# PARKPCB.net
KiCad netlist of a schematic drawn in EAGLE
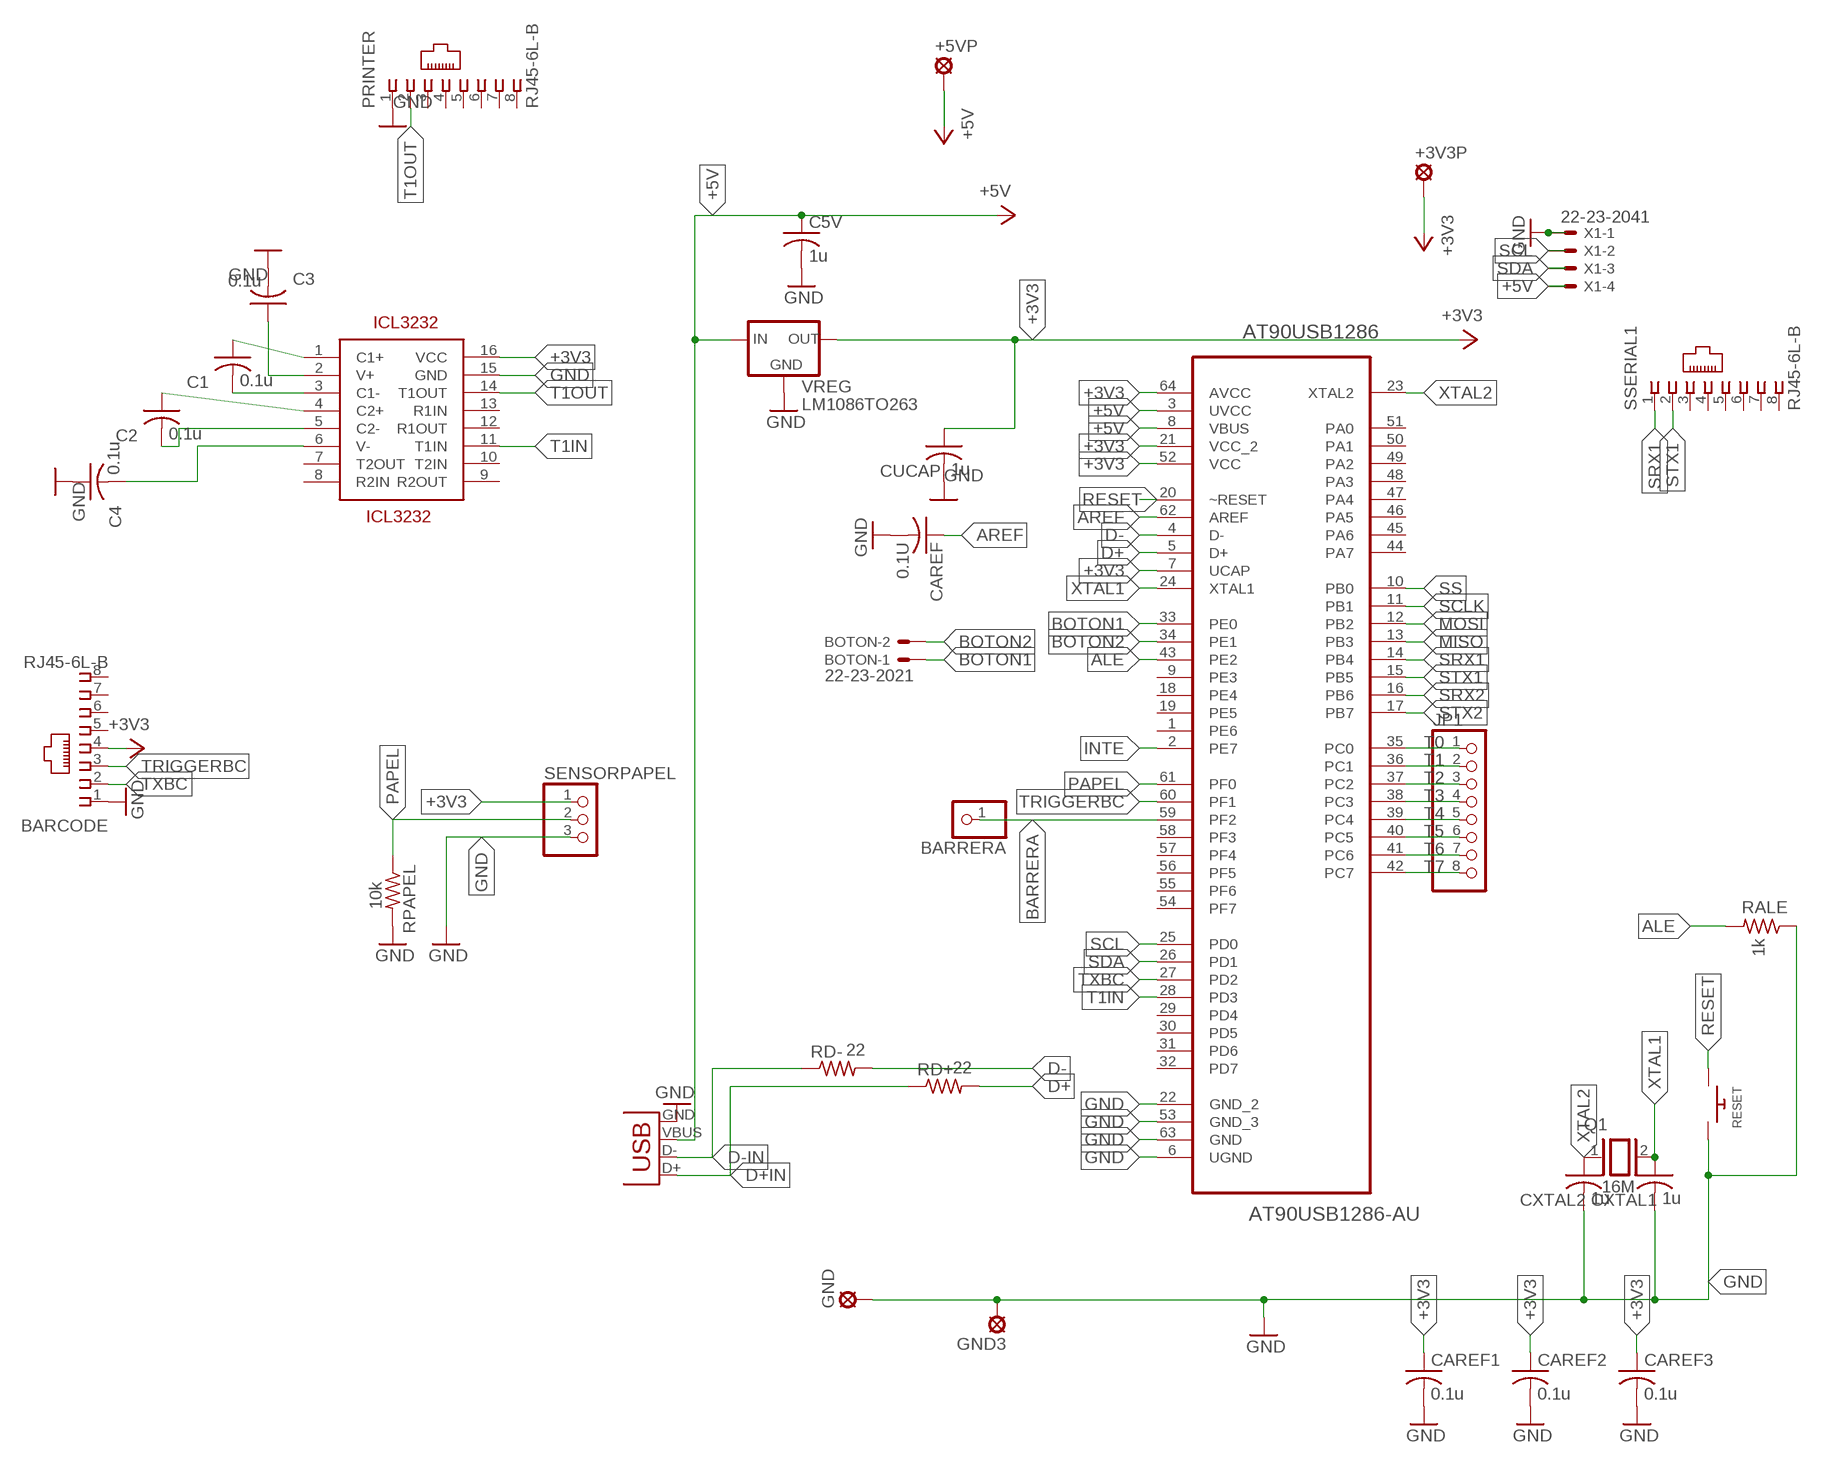
[diagram p0: schematic, sheet 1, part 1 of 2]
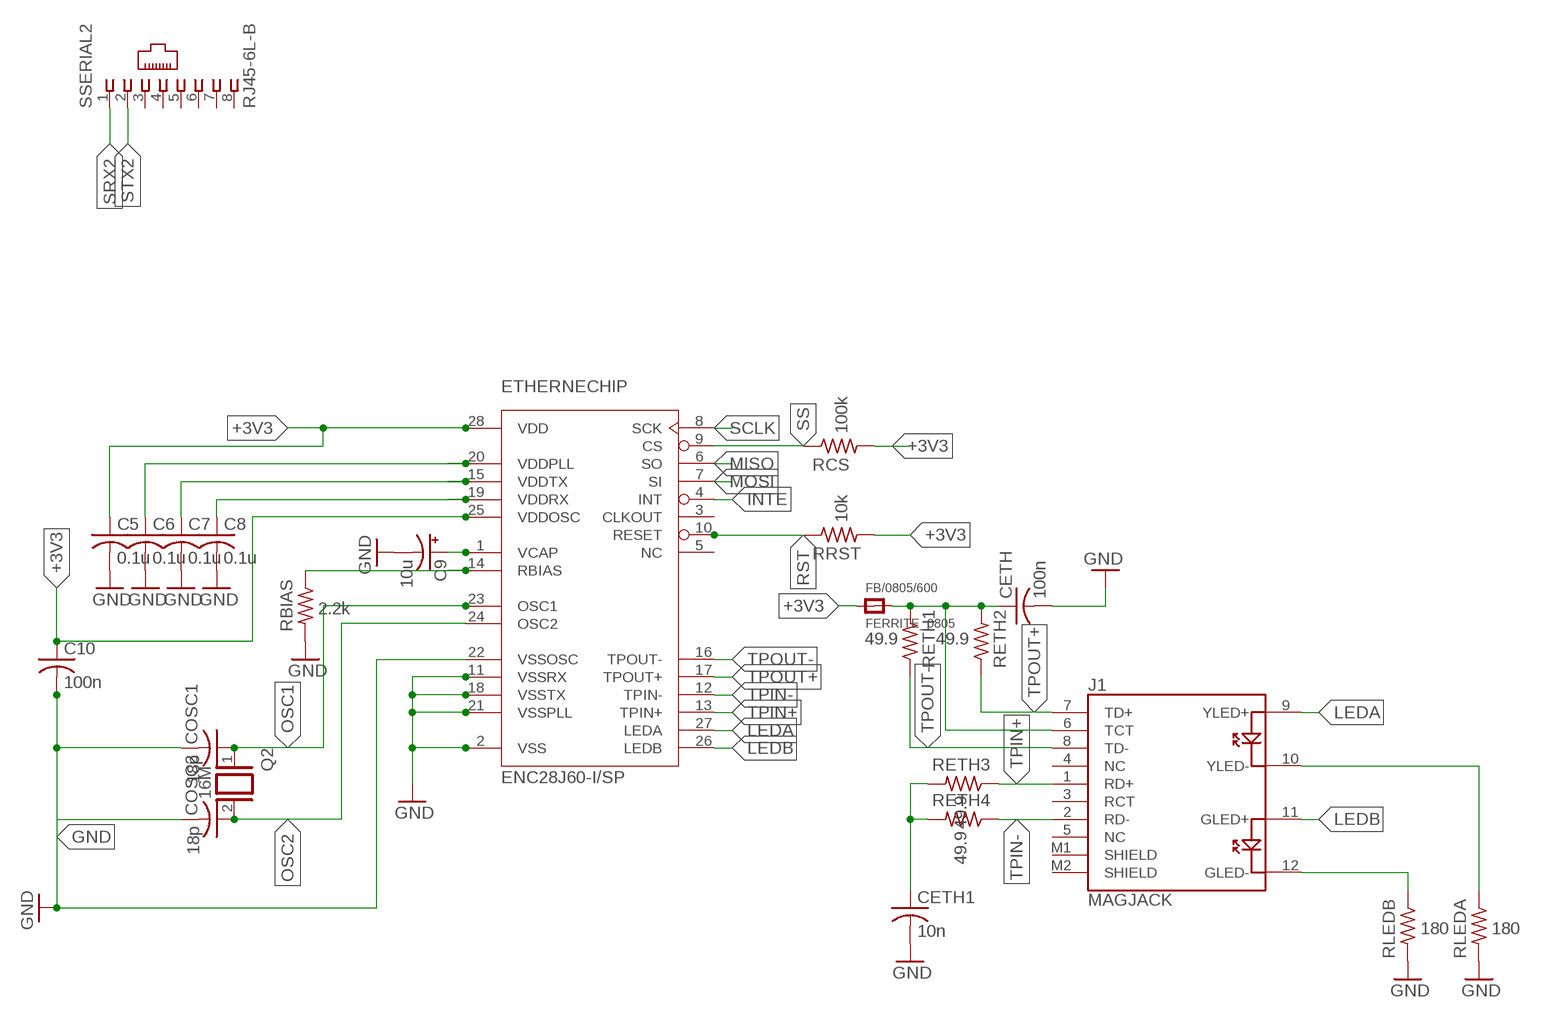
[diagram p1: schematic, sheet 1, part 2 of 2]

(export (version "E")
  (design (tool "Eeschema 10.0.6"))
  (components
    (comp (ref "+3V3P")
      (value "LSP10")
      (footprint "eagle-import:LSP10")
      (libsource (lib "eagle-import") (part "LSP10"))
    )
    (comp (ref "+5VP")
      (value "LSP10")
      (footprint "eagle-import:LSP10")
      (libsource (lib "eagle-import") (part "LSP10"))
    )
    (comp (ref "AT90USB1286")
      (value "AT90USB1286-AU")
      (footprint "eagle-import:QFP80P1600X1600X120-64N")
      (libsource (lib "eagle-import") (part "AT90USB1286-AU"))
    )
    (comp (ref "BARCODE")
      (value "RJ45-6L-B")
      (footprint "eagle-import:RJ45-NO-SHIELD")
      (libsource (lib "eagle-import") (part "RJ45-6L-B"))
    )
    (comp (ref "BARRERA")
      (value "PINHD-1X1")
      (footprint "eagle-import:1X01")
      (libsource (lib "eagle-import") (part "PINHD-1X1"))
    )
    (comp (ref "BOTON")
      (value "22-23-2021")
      (footprint "eagle-import:22-23-2021")
      (fields (field (name "MF") "MOLEX"))
      (libsource (lib "eagle-import") (part "22-23-2021"))
    )
    (comp (ref "C1")
      (value "0.1u")
      (footprint "eagle-import:C050-030X075")
      (libsource (lib "eagle-import") (part "C-US050-030X075"))
    )
    (comp (ref "C2")
      (value "0.1u")
      (footprint "eagle-import:C050-030X075")
      (libsource (lib "eagle-import") (part "C-US050-030X075"))
    )
    (comp (ref "C3")
      (value "0.1u")
      (footprint "eagle-import:C050-030X075")
      (libsource (lib "eagle-import") (part "C-US050-030X075"))
    )
    (comp (ref "C4")
      (value "0.1u")
      (footprint "eagle-import:C050-030X075")
      (libsource (lib "eagle-import") (part "C-US050-030X075"))
    )
    (comp (ref "C5")
      (value "0.1u")
      (footprint "eagle-import:C050-030X075")
      (libsource (lib "eagle-import") (part "C-US050-030X075"))
    )
    (comp (ref "C5V")
      (value "1u")
      (footprint "eagle-import:C050-030X075")
      (libsource (lib "eagle-import") (part "C-US050-030X075"))
    )
    (comp (ref "C6")
      (value "0.1u")
      (footprint "eagle-import:C050-030X075")
      (libsource (lib "eagle-import") (part "C-US050-030X075"))
    )
    (comp (ref "C7")
      (value "0.1u")
      (footprint "eagle-import:C050-030X075")
      (libsource (lib "eagle-import") (part "C-US050-030X075"))
    )
    (comp (ref "C8")
      (value "0.1u")
      (footprint "eagle-import:C050-030X075")
      (libsource (lib "eagle-import") (part "C-US050-030X075"))
    )
    (comp (ref "C9")
      (value "10u")
      (footprint "eagle-import:B45181B")
      (libsource (lib "eagle-import") (part "CPOL-USB45181B"))
    )
    (comp (ref "C10")
      (value "100n")
      (footprint "eagle-import:C050-030X075")
      (libsource (lib "eagle-import") (part "C-US050-030X075"))
    )
    (comp (ref "CAREF")
      (value "0.1U")
      (footprint "eagle-import:C050-030X075")
      (libsource (lib "eagle-import") (part "C-US050-030X075"))
    )
    (comp (ref "CAREF1")
      (value "0.1u")
      (footprint "eagle-import:C050-030X075")
      (libsource (lib "eagle-import") (part "C-US050-030X075"))
    )
    (comp (ref "CAREF2")
      (value "0.1u")
      (footprint "eagle-import:C050-030X075")
      (libsource (lib "eagle-import") (part "C-US050-030X075"))
    )
    (comp (ref "CAREF3")
      (value "0.1u")
      (footprint "eagle-import:C050-030X075")
      (libsource (lib "eagle-import") (part "C-US050-030X075"))
    )
    (comp (ref "CETH")
      (value "100n")
      (footprint "eagle-import:C050-030X075")
      (libsource (lib "eagle-import") (part "C-US050-030X075"))
    )
    (comp (ref "CETH1")
      (value "10n")
      (footprint "eagle-import:C050-030X075")
      (libsource (lib "eagle-import") (part "C-US050-030X075"))
    )
    (comp (ref "COSC1")
      (value "18p")
      (footprint "eagle-import:C050-030X075")
      (libsource (lib "eagle-import") (part "C-US050-030X075"))
    )
    (comp (ref "COSC2")
      (value "18p")
      (footprint "eagle-import:C050-030X075")
      (libsource (lib "eagle-import") (part "C-US050-030X075"))
    )
    (comp (ref "CUCAP")
      (value "1u")
      (footprint "eagle-import:C050-030X075")
      (libsource (lib "eagle-import") (part "C-US050-030X075"))
    )
    (comp (ref "CXTAL1")
      (value "1u")
      (footprint "eagle-import:C050-030X075")
      (libsource (lib "eagle-import") (part "C-US050-030X075"))
    )
    (comp (ref "CXTAL2")
      (value "1u")
      (footprint "eagle-import:C050-030X075")
      (libsource (lib "eagle-import") (part "C-US050-030X075"))
    )
    (comp (ref "ETHERNECHIP")
      (value "ENC28J60-I/SP")
      (footprint "eagle-import:DIP28")
      (libsource (lib "eagle-import") (part "ENC28J60-I/SP"))
    )
    (comp (ref "FB/0805/600")
      (value "FERRITE_0805")
      (footprint "eagle-import:_0805")
      (libsource (lib "eagle-import") (part "FERRITE_0805"))
    )
    (comp (ref "GND")
      (value "LSP10")
      (footprint "eagle-import:LSP10")
      (libsource (lib "eagle-import") (part "LSP10"))
    )
    (comp (ref "GND3")
      (value "LSP10")
      (footprint "eagle-import:LSP10")
      (libsource (lib "eagle-import") (part "LSP10"))
    )
    (comp (ref "ICL3232")
      (value "ICL3232")
      (footprint "eagle-import:DIL16")
      (fields (field (name "MF") "Intersil"))
      (libsource (lib "eagle-import") (part "ICL3232"))
    )
    (comp (ref "J1")
      (value "MAGJACK")
      (footprint "eagle-import:MAGJACK")
      (libsource (lib "eagle-import") (part "MAGJACK"))
    )
    (comp (ref "JP1")
      (value "PINHD-1X8BIG")
      (footprint "eagle-import:1X08-BIG")
      (libsource (lib "eagle-import") (part "PINHD-1X8BIG"))
    )
    (comp (ref "PRINTER")
      (value "RJ45-6L-B")
      (footprint "eagle-import:RJ45-NO-SHIELD")
      (libsource (lib "eagle-import") (part "RJ45-6L-B"))
    )
    (comp (ref "Q1")
      (value "16M")
      (footprint "eagle-import:QS")
      (libsource (lib "eagle-import") (part "XTAL/S"))
    )
    (comp (ref "Q2")
      (value "16M")
      (footprint "eagle-import:QS")
      (libsource (lib "eagle-import") (part "XTAL/S"))
    )
    (comp (ref "RALE")
      (value "1k")
      (footprint "eagle-import:0309_12")
      (libsource (lib "eagle-import") (part "R-US_0309/12"))
    )
    (comp (ref "RBIAS")
      (value "2.2k")
      (footprint "eagle-import:0309_12")
      (libsource (lib "eagle-import") (part "R-US_0309/12"))
    )
    (comp (ref "RCS")
      (value "100k")
      (footprint "eagle-import:0309_12")
      (libsource (lib "eagle-import") (part "R-US_0309/12"))
    )
    (comp (ref "RD+")
      (value "22")
      (footprint "eagle-import:0309_12")
      (libsource (lib "eagle-import") (part "R-US_0309/12"))
    )
    (comp (ref "RD-")
      (value "22")
      (footprint "eagle-import:0309_12")
      (libsource (lib "eagle-import") (part "R-US_0309/12"))
    )
    (comp (ref "RESET")
      (value "SWITCH_PUSHBUTTONC&K_KSS")
      (footprint "eagle-import:BTN_CK_KSS")
      (libsource (lib "eagle-import") (part "SWITCH_PUSHBUTTONC&K_KSS"))
    )
    (comp (ref "RETH1")
      (value "49.9")
      (footprint "eagle-import:0309_12")
      (libsource (lib "eagle-import") (part "R-US_0309/12"))
    )
    (comp (ref "RETH2")
      (value "49.9")
      (footprint "eagle-import:0309_12")
      (libsource (lib "eagle-import") (part "R-US_0309/12"))
    )
    (comp (ref "RETH3")
      (value "49.9")
      (footprint "eagle-import:0309_12")
      (libsource (lib "eagle-import") (part "R-US_0309/12"))
    )
    (comp (ref "RETH4")
      (value "49.9")
      (footprint "eagle-import:0309_12")
      (libsource (lib "eagle-import") (part "R-US_0309/12"))
    )
    (comp (ref "RLEDA")
      (value "180")
      (footprint "eagle-import:0309_12")
      (libsource (lib "eagle-import") (part "R-US_0309/12"))
    )
    (comp (ref "RLEDB")
      (value "180")
      (footprint "eagle-import:0309_12")
      (libsource (lib "eagle-import") (part "R-US_0309/12"))
    )
    (comp (ref "RPAPEL")
      (value "10k")
      (footprint "eagle-import:0309_12")
      (libsource (lib "eagle-import") (part "R-US_0309/12"))
    )
    (comp (ref "RRST")
      (value "10k")
      (footprint "eagle-import:0309_12")
      (libsource (lib "eagle-import") (part "R-US_0309/12"))
    )
    (comp (ref "SENSORPAPEL")
      (value "PINHD-1X3")
      (footprint "eagle-import:1X03")
      (libsource (lib "eagle-import") (part "PINHD-1X3"))
    )
    (comp (ref "SSERIAL1")
      (value "RJ45-6L-B")
      (footprint "eagle-import:RJ45-NO-SHIELD")
      (libsource (lib "eagle-import") (part "RJ45-6L-B"))
    )
    (comp (ref "SSERIAL2")
      (value "RJ45-6L-B")
      (footprint "eagle-import:RJ45-NO-SHIELD")
      (libsource (lib "eagle-import") (part "RJ45-6L-B"))
    )
    (comp (ref "USB")
      (value "USB-MB-S")
      (footprint "eagle-import:USB-MB-S")
      (libsource (lib "eagle-import") (part "USB-MB-S"))
    )
    (comp (ref "VREG")
      (value "LM1086TO263")
      (footprint "eagle-import:TO263")
      (libsource (lib "eagle-import") (part "LM1086TO263"))
    )
    (comp (ref "X1")
      (value "22-23-2041")
      (footprint "eagle-import:22-23-2041")
      (fields (field (name "MF") "MOLEX"))
      (libsource (lib "eagle-import") (part "22-23-2041"))
    )
  )
  (nets
    (net (code "1") (name "+3V3") (class "Default")
      (node (ref "+3V3P") (pin "MP") (pinfunction "MP_MP") (pintype "passive"))
      (node (ref "AT90USB1286") (pin "21") (pinfunction "VCC_2_21") (pintype "power_in"))
      (node (ref "AT90USB1286") (pin "52") (pinfunction "VCC_52") (pintype "power_in"))
      (node (ref "AT90USB1286") (pin "64") (pinfunction "AVCC_64") (pintype "power_in"))
      (node (ref "AT90USB1286") (pin "7") (pinfunction "UCAP_7") (pintype "passive"))
      (node (ref "BARCODE") (pin "4") (pinfunction "4_4") (pintype "passive"))
      (node (ref "C10") (pin "1") (pinfunction "1_1") (pintype "passive"))
      (node (ref "C5") (pin "1") (pinfunction "1_1") (pintype "passive"))
      (node (ref "CAREF1") (pin "1") (pinfunction "1_1") (pintype "passive"))
      (node (ref "CAREF2") (pin "1") (pinfunction "1_1") (pintype "passive"))
      (node (ref "CAREF3") (pin "1") (pinfunction "1_1") (pintype "passive"))
      (node (ref "CUCAP") (pin "1") (pinfunction "1_1") (pintype "passive"))
      (node (ref "ETHERNECHIP") (pin "25") (pinfunction "VDDOSC_25") (pintype "power_in"))
      (node (ref "ETHERNECHIP") (pin "28") (pinfunction "VDD_28") (pintype "power_in"))
      (node (ref "FB/0805/600") (pin "1") (pinfunction "P$1_1") (pintype "passive"))
      (node (ref "ICL3232") (pin "16") (pinfunction "VCC_16") (pintype "bidirectional"))
      (node (ref "RCS") (pin "2") (pinfunction "2_2") (pintype "passive"))
      (node (ref "RRST") (pin "2") (pinfunction "2_2") (pintype "passive"))
      (node (ref "SENSORPAPEL") (pin "1") (pinfunction "1_1") (pintype "passive"))
      (node (ref "VREG") (pin "2") (pinfunction "OUT_2") (pintype "passive"))
    )
    (net (code "2") (name "+5V") (class "Default")
      (node (ref "+5VP") (pin "MP") (pinfunction "MP_MP") (pintype "passive"))
      (node (ref "AT90USB1286") (pin "3") (pinfunction "UVCC_3") (pintype "power_in"))
      (node (ref "AT90USB1286") (pin "8") (pinfunction "VBUS_8") (pintype "power_in"))
      (node (ref "C5V") (pin "1") (pinfunction "1_1") (pintype "passive"))
      (node (ref "USB") (pin "VBUS") (pinfunction "VBUS_VBUS") (pintype "bidirectional"))
      (node (ref "VREG") (pin "3") (pinfunction "IN_3") (pintype "input"))
      (node (ref "X1") (pin "4") (pinfunction "S_4") (pintype "passive"))
    )
    (net (code "3") (name "/T0") (class "Default")
      (node (ref "AT90USB1286") (pin "35") (pinfunction "PC0_35") (pintype "bidirectional"))
      (node (ref "JP1") (pin "1") (pinfunction "1_1") (pintype "passive"))
    )
    (net (code "4") (name "/T1") (class "Default")
      (node (ref "AT90USB1286") (pin "36") (pinfunction "PC1_36") (pintype "bidirectional"))
      (node (ref "JP1") (pin "2") (pinfunction "2_2") (pintype "passive"))
    )
    (net (code "5") (name "/T2") (class "Default")
      (node (ref "AT90USB1286") (pin "37") (pinfunction "PC2_37") (pintype "bidirectional"))
      (node (ref "JP1") (pin "3") (pinfunction "3_3") (pintype "passive"))
    )
    (net (code "6") (name "/T3") (class "Default")
      (node (ref "AT90USB1286") (pin "38") (pinfunction "PC3_38") (pintype "bidirectional"))
      (node (ref "JP1") (pin "4") (pinfunction "4_4") (pintype "passive"))
    )
    (net (code "7") (name "/T4") (class "Default")
      (node (ref "AT90USB1286") (pin "39") (pinfunction "PC4_39") (pintype "bidirectional"))
      (node (ref "JP1") (pin "5") (pinfunction "5_5") (pintype "passive"))
    )
    (net (code "8") (name "/T5") (class "Default")
      (node (ref "AT90USB1286") (pin "40") (pinfunction "PC5_40") (pintype "bidirectional"))
      (node (ref "JP1") (pin "6") (pinfunction "6_6") (pintype "passive"))
    )
    (net (code "9") (name "/T6") (class "Default")
      (node (ref "AT90USB1286") (pin "41") (pinfunction "PC6_41") (pintype "bidirectional"))
      (node (ref "JP1") (pin "7") (pinfunction "7_7") (pintype "passive"))
    )
    (net (code "10") (name "/T7") (class "Default")
      (node (ref "AT90USB1286") (pin "42") (pinfunction "PC7_42") (pintype "bidirectional"))
      (node (ref "JP1") (pin "8") (pinfunction "8_8") (pintype "passive"))
    )
    (net (code "11") (name "ALE") (class "Default")
      (node (ref "AT90USB1286") (pin "43") (pinfunction "PE2_43") (pintype "bidirectional"))
      (node (ref "RALE") (pin "2") (pinfunction "2_2") (pintype "passive"))
    )
    (net (code "12") (name "AREF") (class "Default")
      (node (ref "AT90USB1286") (pin "62") (pinfunction "AREF_62") (pintype "input"))
      (node (ref "CAREF") (pin "1") (pinfunction "1_1") (pintype "passive"))
    )
    (net (code "13") (name "BARRERA") (class "Default")
      (node (ref "AT90USB1286") (pin "59") (pinfunction "PF2_59") (pintype "bidirectional"))
      (node (ref "BARRERA") (pin "1") (pinfunction "1_1") (pintype "passive"))
    )
    (net (code "14") (name "BOTON1") (class "Default")
      (node (ref "AT90USB1286") (pin "33") (pinfunction "PE0_33") (pintype "bidirectional"))
      (node (ref "BOTON") (pin "1") (pinfunction "S_1") (pintype "passive"))
    )
    (net (code "15") (name "BOTON2") (class "Default")
      (node (ref "AT90USB1286") (pin "34") (pinfunction "PE1_34") (pintype "bidirectional"))
      (node (ref "BOTON") (pin "2") (pinfunction "S_2") (pintype "passive"))
    )
    (net (code "16") (name "D+") (class "Default")
      (node (ref "AT90USB1286") (pin "5") (pinfunction "D+_5") (pintype "input"))
      (node (ref "RD+") (pin "2") (pinfunction "2_2") (pintype "passive"))
    )
    (net (code "17") (name "D+IN") (class "Default")
      (node (ref "RD+") (pin "1") (pinfunction "1_1") (pintype "passive"))
      (node (ref "USB") (pin "D+") (pinfunction "D+_D+") (pintype "bidirectional"))
    )
    (net (code "18") (name "D-") (class "Default")
      (node (ref "AT90USB1286") (pin "4") (pinfunction "D-_4") (pintype "input"))
      (node (ref "RD-") (pin "2") (pinfunction "2_2") (pintype "passive"))
    )
    (net (code "19") (name "D-IN") (class "Default")
      (node (ref "RD-") (pin "1") (pinfunction "1_1") (pintype "passive"))
      (node (ref "USB") (pin "D-") (pinfunction "D-_D-") (pintype "bidirectional"))
    )
    (net (code "20") (name "GND") (class "Default")
      (node (ref "AT90USB1286") (pin "22") (pinfunction "GND_2_22") (pintype "passive"))
      (node (ref "AT90USB1286") (pin "53") (pinfunction "GND_3_53") (pintype "passive"))
      (node (ref "AT90USB1286") (pin "6") (pinfunction "UGND_6") (pintype "passive"))
      (node (ref "AT90USB1286") (pin "63") (pinfunction "GND_63") (pintype "passive"))
      (node (ref "BARCODE") (pin "1") (pinfunction "1_1") (pintype "passive"))
      (node (ref "C10") (pin "2") (pinfunction "2_2") (pintype "passive"))
      (node (ref "C3") (pin "2") (pinfunction "2_2") (pintype "passive"))
      (node (ref "C4") (pin "1") (pinfunction "1_1") (pintype "passive"))
      (node (ref "C5") (pin "2") (pinfunction "2_2") (pintype "passive"))
      (node (ref "C5V") (pin "2") (pinfunction "2_2") (pintype "passive"))
      (node (ref "C6") (pin "2") (pinfunction "2_2") (pintype "passive"))
      (node (ref "C7") (pin "2") (pinfunction "2_2") (pintype "passive"))
      (node (ref "C8") (pin "2") (pinfunction "2_2") (pintype "passive"))
      (node (ref "C9") (pin "-") (pinfunction "-_-") (pintype "passive"))
      (node (ref "CAREF") (pin "2") (pinfunction "2_2") (pintype "passive"))
      (node (ref "CAREF1") (pin "2") (pinfunction "2_2") (pintype "passive"))
      (node (ref "CAREF2") (pin "2") (pinfunction "2_2") (pintype "passive"))
      (node (ref "CAREF3") (pin "2") (pinfunction "2_2") (pintype "passive"))
      (node (ref "CETH") (pin "2") (pinfunction "2_2") (pintype "passive"))
      (node (ref "CETH1") (pin "2") (pinfunction "2_2") (pintype "passive"))
      (node (ref "COSC1") (pin "2") (pinfunction "2_2") (pintype "passive"))
      (node (ref "COSC2") (pin "2") (pinfunction "2_2") (pintype "passive"))
      (node (ref "CUCAP") (pin "2") (pinfunction "2_2") (pintype "passive"))
      (node (ref "CXTAL1") (pin "2") (pinfunction "2_2") (pintype "passive"))
      (node (ref "CXTAL2") (pin "2") (pinfunction "2_2") (pintype "passive"))
      (node (ref "ETHERNECHIP") (pin "11") (pinfunction "VSSRX_11") (pintype "power_in"))
      (node (ref "ETHERNECHIP") (pin "18") (pinfunction "VSSTX_18") (pintype "power_in"))
      (node (ref "ETHERNECHIP") (pin "2") (pinfunction "VSS_2") (pintype "power_in"))
      (node (ref "ETHERNECHIP") (pin "21") (pinfunction "VSSPLL_21") (pintype "power_in"))
      (node (ref "ETHERNECHIP") (pin "22") (pinfunction "VSSOSC_22") (pintype "power_in"))
      (node (ref "GND") (pin "MP") (pinfunction "MP_MP") (pintype "passive"))
      (node (ref "GND3") (pin "MP") (pinfunction "MP_MP") (pintype "passive"))
      (node (ref "ICL3232") (pin "15") (pinfunction "GND_15") (pintype "bidirectional"))
      (node (ref "PRINTER") (pin "1") (pinfunction "1_1") (pintype "passive"))
      (node (ref "RALE") (pin "1") (pinfunction "1_1") (pintype "passive"))
      (node (ref "RBIAS") (pin "2") (pinfunction "2_2") (pintype "passive"))
      (node (ref "RESET") (pin "P$2") (pinfunction "P$2_P$2") (pintype "passive"))
      (node (ref "RLEDA") (pin "2") (pinfunction "2_2") (pintype "passive"))
      (node (ref "RLEDB") (pin "2") (pinfunction "2_2") (pintype "passive"))
      (node (ref "RPAPEL") (pin "2") (pinfunction "2_2") (pintype "passive"))
      (node (ref "SENSORPAPEL") (pin "3") (pinfunction "3_3") (pintype "passive"))
      (node (ref "USB") (pin "GND") (pinfunction "GND_GND") (pintype "bidirectional"))
      (node (ref "VREG") (pin "1") (pinfunction "GND_1") (pintype "input"))
      (node (ref "X1") (pin "1") (pinfunction "S_1") (pintype "passive"))
    )
    (net (code "21") (name "INTE") (class "Default")
      (node (ref "AT90USB1286") (pin "2") (pinfunction "PE7_2") (pintype "bidirectional"))
      (node (ref "ETHERNECHIP") (pin "4") (pinfunction "INT_4") (pintype "output"))
    )
    (net (code "22") (name "LEDA") (class "Default")
      (node (ref "ETHERNECHIP") (pin "27") (pinfunction "LEDA_27") (pintype "output"))
      (node (ref "J1") (pin "9") (pinfunction "YLED+_9") (pintype "bidirectional"))
    )
    (net (code "23") (name "LEDB") (class "Default")
      (node (ref "ETHERNECHIP") (pin "26") (pinfunction "LEDB_26") (pintype "output"))
      (node (ref "J1") (pin "11") (pinfunction "GLED+_11") (pintype "bidirectional"))
    )
    (net (code "24") (name "MISO") (class "Default")
      (node (ref "AT90USB1286") (pin "13") (pinfunction "PB3_13") (pintype "bidirectional"))
      (node (ref "ETHERNECHIP") (pin "6") (pinfunction "SO_6") (pintype "output"))
    )
    (net (code "25") (name "MOSI") (class "Default")
      (node (ref "AT90USB1286") (pin "12") (pinfunction "PB2_12") (pintype "bidirectional"))
      (node (ref "ETHERNECHIP") (pin "7") (pinfunction "SI_7") (pintype "input"))
    )
    (net (code "26") (name "Net-(CETH1-Pad1)") (class "Default")
      (node (ref "CETH1") (pin "1") (pinfunction "1_1") (pintype "passive"))
      (node (ref "RETH3") (pin "2") (pinfunction "2_2") (pintype "passive"))
      (node (ref "RETH4") (pin "2") (pinfunction "2_2") (pintype "passive"))
    )
    (net (code "27") (name "Net-(ETHERNECHIP-RBIAS)") (class "Default")
      (node (ref "ETHERNECHIP") (pin "14") (pinfunction "RBIAS_14") (pintype "input"))
      (node (ref "RBIAS") (pin "1") (pinfunction "1_1") (pintype "passive"))
    )
    (net (code "28") (name "Net-(ETHERNECHIP-VCAP)") (class "Default")
      (node (ref "C9") (pin "+") (pinfunction "+_+") (pintype "passive"))
      (node (ref "ETHERNECHIP") (pin "1") (pinfunction "VCAP_1") (pintype "input"))
    )
    (net (code "29") (name "Net-(ETHERNECHIP-VDDPLL)") (class "Default")
      (node (ref "C6") (pin "1") (pinfunction "1_1") (pintype "passive"))
      (node (ref "ETHERNECHIP") (pin "20") (pinfunction "VDDPLL_20") (pintype "power_in"))
    )
    (net (code "30") (name "Net-(ETHERNECHIP-VDDRX)") (class "Default")
      (node (ref "C8") (pin "1") (pinfunction "1_1") (pintype "passive"))
      (node (ref "ETHERNECHIP") (pin "19") (pinfunction "VDDRX_19") (pintype "power_in"))
    )
    (net (code "31") (name "Net-(ETHERNECHIP-VDDTX)") (class "Default")
      (node (ref "C7") (pin "1") (pinfunction "1_1") (pintype "passive"))
      (node (ref "ETHERNECHIP") (pin "15") (pinfunction "VDDTX_15") (pintype "power_in"))
    )
    (net (code "32") (name "Net-(FB/0805/600-P$2)") (class "Default")
      (node (ref "CETH") (pin "1") (pinfunction "1_1") (pintype "passive"))
      (node (ref "FB/0805/600") (pin "2") (pinfunction "P$2_2") (pintype "passive"))
      (node (ref "J1") (pin "6") (pinfunction "TCT_6") (pintype "bidirectional"))
      (node (ref "RETH1") (pin "2") (pinfunction "2_2") (pintype "passive"))
      (node (ref "RETH2") (pin "2") (pinfunction "2_2") (pintype "passive"))
    )
    (net (code "33") (name "Net-(ICL3232-C1+)") (class "Default")
      (node (ref "C1") (pin "1") (pinfunction "1_1") (pintype "passive"))
      (node (ref "ICL3232") (pin "1") (pinfunction "C1+_1") (pintype "bidirectional"))
    )
    (net (code "34") (name "Net-(ICL3232-C1-)") (class "Default")
      (node (ref "C1") (pin "2") (pinfunction "2_2") (pintype "passive"))
      (node (ref "ICL3232") (pin "3") (pinfunction "C1-_3") (pintype "bidirectional"))
    )
    (net (code "35") (name "Net-(ICL3232-C2+)") (class "Default")
      (node (ref "C2") (pin "1") (pinfunction "1_1") (pintype "passive"))
      (node (ref "ICL3232") (pin "4") (pinfunction "C2+_4") (pintype "bidirectional"))
    )
    (net (code "36") (name "Net-(ICL3232-C2-)") (class "Default")
      (node (ref "C2") (pin "2") (pinfunction "2_2") (pintype "passive"))
      (node (ref "ICL3232") (pin "5") (pinfunction "C2-_5") (pintype "bidirectional"))
    )
    (net (code "37") (name "Net-(ICL3232-V+)") (class "Default")
      (node (ref "C3") (pin "1") (pinfunction "1_1") (pintype "passive"))
      (node (ref "ICL3232") (pin "2") (pinfunction "V+_2") (pintype "bidirectional"))
    )
    (net (code "38") (name "Net-(ICL3232-V-)") (class "Default")
      (node (ref "C4") (pin "2") (pinfunction "2_2") (pintype "passive"))
      (node (ref "ICL3232") (pin "6") (pinfunction "V-_6") (pintype "bidirectional"))
    )
    (net (code "39") (name "Net-(J1-GLED-)") (class "Default")
      (node (ref "J1") (pin "12") (pinfunction "GLED-_12") (pintype "bidirectional"))
      (node (ref "RLEDB") (pin "1") (pinfunction "1_1") (pintype "passive"))
    )
    (net (code "40") (name "Net-(J1-YLED-)") (class "Default")
      (node (ref "J1") (pin "10") (pinfunction "YLED-_10") (pintype "bidirectional"))
      (node (ref "RLEDA") (pin "1") (pinfunction "1_1") (pintype "passive"))
    )
    (net (code "41") (name "OSC1") (class "Default")
      (node (ref "COSC1") (pin "1") (pinfunction "1_1") (pintype "passive"))
      (node (ref "ETHERNECHIP") (pin "23") (pinfunction "OSC1_23") (pintype "bidirectional"))
      (node (ref "Q2") (pin "1") (pinfunction "1_1") (pintype "passive"))
    )
    (net (code "42") (name "OSC2") (class "Default")
      (node (ref "COSC2") (pin "1") (pinfunction "1_1") (pintype "passive"))
      (node (ref "ETHERNECHIP") (pin "24") (pinfunction "OSC2_24") (pintype "bidirectional"))
      (node (ref "Q2") (pin "2") (pinfunction "2_2") (pintype "passive"))
    )
    (net (code "43") (name "PAPEL") (class "Default")
      (node (ref "AT90USB1286") (pin "61") (pinfunction "PF0_61") (pintype "bidirectional"))
      (node (ref "RPAPEL") (pin "1") (pinfunction "1_1") (pintype "passive"))
      (node (ref "SENSORPAPEL") (pin "2") (pinfunction "2_2") (pintype "passive"))
    )
    (net (code "44") (name "RESET") (class "Default")
      (node (ref "AT90USB1286") (pin "20") (pinfunction "~{RESET}_20") (pintype "input"))
      (node (ref "RESET") (pin "P$1") (pinfunction "P$1_P$1") (pintype "passive"))
    )
    (net (code "45") (name "RST") (class "Default")
      (node (ref "ETHERNECHIP") (pin "10") (pinfunction "RESET_10") (pintype "input"))
      (node (ref "RRST") (pin "1") (pinfunction "1_1") (pintype "passive"))
    )
    (net (code "46") (name "SCL") (class "Default")
      (node (ref "AT90USB1286") (pin "25") (pinfunction "PD0_25") (pintype "bidirectional"))
      (node (ref "X1") (pin "2") (pinfunction "S_2") (pintype "passive"))
    )
    (net (code "47") (name "SCLK") (class "Default")
      (node (ref "AT90USB1286") (pin "11") (pinfunction "PB1_11") (pintype "bidirectional"))
      (node (ref "ETHERNECHIP") (pin "8") (pinfunction "SCK_8") (pintype "input"))
    )
    (net (code "48") (name "SDA") (class "Default")
      (node (ref "AT90USB1286") (pin "26") (pinfunction "PD1_26") (pintype "bidirectional"))
      (node (ref "X1") (pin "3") (pinfunction "S_3") (pintype "passive"))
    )
    (net (code "49") (name "SRX1") (class "Default")
      (node (ref "AT90USB1286") (pin "14") (pinfunction "PB4_14") (pintype "bidirectional"))
      (node (ref "SSERIAL1") (pin "1") (pinfunction "1_1") (pintype "passive"))
    )
    (net (code "50") (name "SRX2") (class "Default")
      (node (ref "AT90USB1286") (pin "16") (pinfunction "PB6_16") (pintype "bidirectional"))
      (node (ref "SSERIAL2") (pin "1") (pinfunction "1_1") (pintype "passive"))
    )
    (net (code "51") (name "SS") (class "Default")
      (node (ref "AT90USB1286") (pin "10") (pinfunction "PB0_10") (pintype "bidirectional"))
      (node (ref "ETHERNECHIP") (pin "9") (pinfunction "CS_9") (pintype "input"))
      (node (ref "RCS") (pin "1") (pinfunction "1_1") (pintype "passive"))
    )
    (net (code "52") (name "STX1") (class "Default")
      (node (ref "AT90USB1286") (pin "15") (pinfunction "PB5_15") (pintype "bidirectional"))
      (node (ref "SSERIAL1") (pin "2") (pinfunction "2_2") (pintype "passive"))
    )
    (net (code "53") (name "STX2") (class "Default")
      (node (ref "AT90USB1286") (pin "17") (pinfunction "PB7_17") (pintype "bidirectional"))
      (node (ref "SSERIAL2") (pin "2") (pinfunction "2_2") (pintype "passive"))
    )
    (net (code "54") (name "T1IN") (class "Default")
      (node (ref "AT90USB1286") (pin "28") (pinfunction "PD3_28") (pintype "bidirectional"))
      (node (ref "ICL3232") (pin "11") (pinfunction "T1IN_11") (pintype "bidirectional"))
    )
    (net (code "55") (name "T1OUT") (class "Default")
      (node (ref "ICL3232") (pin "14") (pinfunction "T1OUT_14") (pintype "bidirectional"))
      (node (ref "PRINTER") (pin "2") (pinfunction "2_2") (pintype "passive"))
    )
    (net (code "56") (name "TPIN+") (class "Default")
      (node (ref "ETHERNECHIP") (pin "13") (pinfunction "TPIN+_13") (pintype "input"))
      (node (ref "J1") (pin "1") (pinfunction "RD+_1") (pintype "bidirectional"))
      (node (ref "RETH3") (pin "1") (pinfunction "1_1") (pintype "passive"))
    )
    (net (code "57") (name "TPIN-") (class "Default")
      (node (ref "ETHERNECHIP") (pin "12") (pinfunction "TPIN-_12") (pintype "input"))
      (node (ref "J1") (pin "2") (pinfunction "RD-_2") (pintype "bidirectional"))
      (node (ref "RETH4") (pin "1") (pinfunction "1_1") (pintype "passive"))
    )
    (net (code "58") (name "TPOUT+") (class "Default")
      (node (ref "ETHERNECHIP") (pin "17") (pinfunction "TPOUT+_17") (pintype "output"))
      (node (ref "J1") (pin "7") (pinfunction "TD+_7") (pintype "bidirectional"))
      (node (ref "RETH2") (pin "1") (pinfunction "1_1") (pintype "passive"))
    )
    (net (code "59") (name "TPOUT-") (class "Default")
      (node (ref "ETHERNECHIP") (pin "16") (pinfunction "TPOUT-_16") (pintype "output"))
      (node (ref "J1") (pin "8") (pinfunction "TD-_8") (pintype "bidirectional"))
      (node (ref "RETH1") (pin "1") (pinfunction "1_1") (pintype "passive"))
    )
    (net (code "60") (name "TRIGGERBC") (class "Default")
      (node (ref "AT90USB1286") (pin "60") (pinfunction "PF1_60") (pintype "bidirectional"))
      (node (ref "BARCODE") (pin "3") (pinfunction "3_3") (pintype "passive"))
    )
    (net (code "61") (name "TXBC") (class "Default")
      (node (ref "AT90USB1286") (pin "27") (pinfunction "PD2_27") (pintype "bidirectional"))
      (node (ref "BARCODE") (pin "2") (pinfunction "2_2") (pintype "passive"))
    )
    (net (code "62") (name "XTAL1") (class "Default")
      (node (ref "AT90USB1286") (pin "24") (pinfunction "XTAL1_24") (pintype "input"))
      (node (ref "CXTAL1") (pin "1") (pinfunction "1_1") (pintype "passive"))
      (node (ref "Q1") (pin "2") (pinfunction "2_2") (pintype "passive"))
    )
    (net (code "63") (name "XTAL2") (class "Default")
      (node (ref "AT90USB1286") (pin "23") (pinfunction "XTAL2_23") (pintype "output"))
      (node (ref "CXTAL2") (pin "1") (pinfunction "1_1") (pintype "passive"))
      (node (ref "Q1") (pin "1") (pinfunction "1_1") (pintype "passive"))
    )
    (net (code "64") (name "unconnected-(AT90USB1286-PA0-Pad51)") (class "Default")
      (node (ref "AT90USB1286") (pin "51") (pinfunction "PA0_51") (pintype "bidirectional"))
    )
    (net (code "65") (name "unconnected-(AT90USB1286-PA1-Pad50)") (class "Default")
      (node (ref "AT90USB1286") (pin "50") (pinfunction "PA1_50") (pintype "bidirectional"))
    )
    (net (code "66") (name "unconnected-(AT90USB1286-PA2-Pad49)") (class "Default")
      (node (ref "AT90USB1286") (pin "49") (pinfunction "PA2_49") (pintype "bidirectional"))
    )
    (net (code "67") (name "unconnected-(AT90USB1286-PA3-Pad48)") (class "Default")
      (node (ref "AT90USB1286") (pin "48") (pinfunction "PA3_48") (pintype "bidirectional"))
    )
    (net (code "68") (name "unconnected-(AT90USB1286-PA4-Pad47)") (class "Default")
      (node (ref "AT90USB1286") (pin "47") (pinfunction "PA4_47") (pintype "bidirectional"))
    )
    (net (code "69") (name "unconnected-(AT90USB1286-PA5-Pad46)") (class "Default")
      (node (ref "AT90USB1286") (pin "46") (pinfunction "PA5_46") (pintype "bidirectional"))
    )
    (net (code "70") (name "unconnected-(AT90USB1286-PA6-Pad45)") (class "Default")
      (node (ref "AT90USB1286") (pin "45") (pinfunction "PA6_45") (pintype "bidirectional"))
    )
    (net (code "71") (name "unconnected-(AT90USB1286-PA7-Pad44)") (class "Default")
      (node (ref "AT90USB1286") (pin "44") (pinfunction "PA7_44") (pintype "bidirectional"))
    )
    (net (code "72") (name "unconnected-(AT90USB1286-PD4-Pad29)") (class "Default")
      (node (ref "AT90USB1286") (pin "29") (pinfunction "PD4_29") (pintype "bidirectional"))
    )
    (net (code "73") (name "unconnected-(AT90USB1286-PD5-Pad30)") (class "Default")
      (node (ref "AT90USB1286") (pin "30") (pinfunction "PD5_30") (pintype "bidirectional"))
    )
    (net (code "74") (name "unconnected-(AT90USB1286-PD6-Pad31)") (class "Default")
      (node (ref "AT90USB1286") (pin "31") (pinfunction "PD6_31") (pintype "bidirectional"))
    )
    (net (code "75") (name "unconnected-(AT90USB1286-PD7-Pad32)") (class "Default")
      (node (ref "AT90USB1286") (pin "32") (pinfunction "PD7_32") (pintype "bidirectional"))
    )
    (net (code "76") (name "unconnected-(AT90USB1286-PE3-Pad9)") (class "Default")
      (node (ref "AT90USB1286") (pin "9") (pinfunction "PE3_9") (pintype "bidirectional"))
    )
    (net (code "77") (name "unconnected-(AT90USB1286-PE4-Pad18)") (class "Default")
      (node (ref "AT90USB1286") (pin "18") (pinfunction "PE4_18") (pintype "bidirectional"))
    )
    (net (code "78") (name "unconnected-(AT90USB1286-PE5-Pad19)") (class "Default")
      (node (ref "AT90USB1286") (pin "19") (pinfunction "PE5_19") (pintype "bidirectional"))
    )
    (net (code "79") (name "unconnected-(AT90USB1286-PE6-Pad1)") (class "Default")
      (node (ref "AT90USB1286") (pin "1") (pinfunction "PE6_1") (pintype "bidirectional"))
    )
    (net (code "80") (name "unconnected-(AT90USB1286-PF3-Pad58)") (class "Default")
      (node (ref "AT90USB1286") (pin "58") (pinfunction "PF3_58") (pintype "bidirectional"))
    )
    (net (code "81") (name "unconnected-(AT90USB1286-PF4-Pad57)") (class "Default")
      (node (ref "AT90USB1286") (pin "57") (pinfunction "PF4_57") (pintype "bidirectional"))
    )
    (net (code "82") (name "unconnected-(AT90USB1286-PF5-Pad56)") (class "Default")
      (node (ref "AT90USB1286") (pin "56") (pinfunction "PF5_56") (pintype "bidirectional"))
    )
    (net (code "83") (name "unconnected-(AT90USB1286-PF6-Pad55)") (class "Default")
      (node (ref "AT90USB1286") (pin "55") (pinfunction "PF6_55") (pintype "bidirectional"))
    )
    (net (code "84") (name "unconnected-(AT90USB1286-PF7-Pad54)") (class "Default")
      (node (ref "AT90USB1286") (pin "54") (pinfunction "PF7_54") (pintype "bidirectional"))
    )
    (net (code "85") (name "unconnected-(BARCODE-Pad5)") (class "Default")
      (node (ref "BARCODE") (pin "5") (pinfunction "5_5") (pintype "passive"))
    )
    (net (code "86") (name "unconnected-(BARCODE-Pad6)") (class "Default")
      (node (ref "BARCODE") (pin "6") (pinfunction "6_6") (pintype "passive"))
    )
    (net (code "87") (name "unconnected-(BARCODE-Pad7)") (class "Default")
      (node (ref "BARCODE") (pin "7") (pinfunction "7_7") (pintype "passive"))
    )
    (net (code "88") (name "unconnected-(BARCODE-Pad8)") (class "Default")
      (node (ref "BARCODE") (pin "8") (pinfunction "8_8") (pintype "passive"))
    )
    (net (code "89") (name "unconnected-(ETHERNECHIP-CLKOUT-Pad3)") (class "Default")
      (node (ref "ETHERNECHIP") (pin "3") (pinfunction "CLKOUT_3") (pintype "output"))
    )
    (net (code "90") (name "unconnected-(ETHERNECHIP-NC-Pad5)") (class "Default")
      (node (ref "ETHERNECHIP") (pin "5") (pinfunction "NC_5") (pintype "no_connect"))
    )
    (net (code "91") (name "unconnected-(ICL3232-R1IN-Pad13)") (class "Default")
      (node (ref "ICL3232") (pin "13") (pinfunction "R1IN_13") (pintype "bidirectional"))
    )
    (net (code "92") (name "unconnected-(ICL3232-R1OUT-Pad12)") (class "Default")
      (node (ref "ICL3232") (pin "12") (pinfunction "R1OUT_12") (pintype "bidirectional"))
    )
    (net (code "93") (name "unconnected-(ICL3232-R2IN-Pad8)") (class "Default")
      (node (ref "ICL3232") (pin "8") (pinfunction "R2IN_8") (pintype "bidirectional"))
    )
    (net (code "94") (name "unconnected-(ICL3232-R2OUT-Pad9)") (class "Default")
      (node (ref "ICL3232") (pin "9") (pinfunction "R2OUT_9") (pintype "bidirectional"))
    )
    (net (code "95") (name "unconnected-(ICL3232-T2IN-Pad10)") (class "Default")
      (node (ref "ICL3232") (pin "10") (pinfunction "T2IN_10") (pintype "bidirectional"))
    )
    (net (code "96") (name "unconnected-(ICL3232-T2OUT-Pad7)") (class "Default")
      (node (ref "ICL3232") (pin "7") (pinfunction "T2OUT_7") (pintype "bidirectional"))
    )
    (net (code "97") (name "unconnected-(J1-NC-Pad4)") (class "Default")
      (node (ref "J1") (pin "4") (pinfunction "NC_4") (pintype "bidirectional"))
    )
    (net (code "98") (name "unconnected-(J1-NC-Pad5)") (class "Default")
      (node (ref "J1") (pin "5") (pinfunction "NC_5") (pintype "bidirectional"))
    )
    (net (code "99") (name "unconnected-(J1-RCT-Pad3)") (class "Default")
      (node (ref "J1") (pin "3") (pinfunction "RCT_3") (pintype "bidirectional"))
    )
    (net (code "100") (name "unconnected-(J1-SHIELD-PadM1)") (class "Default")
      (node (ref "J1") (pin "M1") (pinfunction "SHIELD_M1") (pintype "bidirectional"))
    )
    (net (code "101") (name "unconnected-(J1-SHIELD-PadM2)") (class "Default")
      (node (ref "J1") (pin "M2") (pinfunction "SHIELD_M2") (pintype "bidirectional"))
    )
    (net (code "102") (name "unconnected-(PRINTER-Pad3)") (class "Default")
      (node (ref "PRINTER") (pin "3") (pinfunction "3_3") (pintype "passive"))
    )
    (net (code "103") (name "unconnected-(PRINTER-Pad4)") (class "Default")
      (node (ref "PRINTER") (pin "4") (pinfunction "4_4") (pintype "passive"))
    )
    (net (code "104") (name "unconnected-(PRINTER-Pad5)") (class "Default")
      (node (ref "PRINTER") (pin "5") (pinfunction "5_5") (pintype "passive"))
    )
    (net (code "105") (name "unconnected-(PRINTER-Pad6)") (class "Default")
      (node (ref "PRINTER") (pin "6") (pinfunction "6_6") (pintype "passive"))
    )
    (net (code "106") (name "unconnected-(PRINTER-Pad7)") (class "Default")
      (node (ref "PRINTER") (pin "7") (pinfunction "7_7") (pintype "passive"))
    )
    (net (code "107") (name "unconnected-(PRINTER-Pad8)") (class "Default")
      (node (ref "PRINTER") (pin "8") (pinfunction "8_8") (pintype "passive"))
    )
    (net (code "108") (name "unconnected-(SSERIAL1-Pad3)") (class "Default")
      (node (ref "SSERIAL1") (pin "3") (pinfunction "3_3") (pintype "passive"))
    )
    (net (code "109") (name "unconnected-(SSERIAL1-Pad4)") (class "Default")
      (node (ref "SSERIAL1") (pin "4") (pinfunction "4_4") (pintype "passive"))
    )
    (net (code "110") (name "unconnected-(SSERIAL1-Pad5)") (class "Default")
      (node (ref "SSERIAL1") (pin "5") (pinfunction "5_5") (pintype "passive"))
    )
    (net (code "111") (name "unconnected-(SSERIAL1-Pad6)") (class "Default")
      (node (ref "SSERIAL1") (pin "6") (pinfunction "6_6") (pintype "passive"))
    )
    (net (code "112") (name "unconnected-(SSERIAL1-Pad7)") (class "Default")
      (node (ref "SSERIAL1") (pin "7") (pinfunction "7_7") (pintype "passive"))
    )
    (net (code "113") (name "unconnected-(SSERIAL1-Pad8)") (class "Default")
      (node (ref "SSERIAL1") (pin "8") (pinfunction "8_8") (pintype "passive"))
    )
    (net (code "114") (name "unconnected-(SSERIAL2-Pad3)") (class "Default")
      (node (ref "SSERIAL2") (pin "3") (pinfunction "3_3") (pintype "passive"))
    )
    (net (code "115") (name "unconnected-(SSERIAL2-Pad4)") (class "Default")
      (node (ref "SSERIAL2") (pin "4") (pinfunction "4_4") (pintype "passive"))
    )
    (net (code "116") (name "unconnected-(SSERIAL2-Pad5)") (class "Default")
      (node (ref "SSERIAL2") (pin "5") (pinfunction "5_5") (pintype "passive"))
    )
    (net (code "117") (name "unconnected-(SSERIAL2-Pad6)") (class "Default")
      (node (ref "SSERIAL2") (pin "6") (pinfunction "6_6") (pintype "passive"))
    )
    (net (code "118") (name "unconnected-(SSERIAL2-Pad7)") (class "Default")
      (node (ref "SSERIAL2") (pin "7") (pinfunction "7_7") (pintype "passive"))
    )
    (net (code "119") (name "unconnected-(SSERIAL2-Pad8)") (class "Default")
      (node (ref "SSERIAL2") (pin "8") (pinfunction "8_8") (pintype "passive"))
    )
  )
)
